# Clock_circuit.net
KiCad netlist of a schematic drawn in Altium Designer
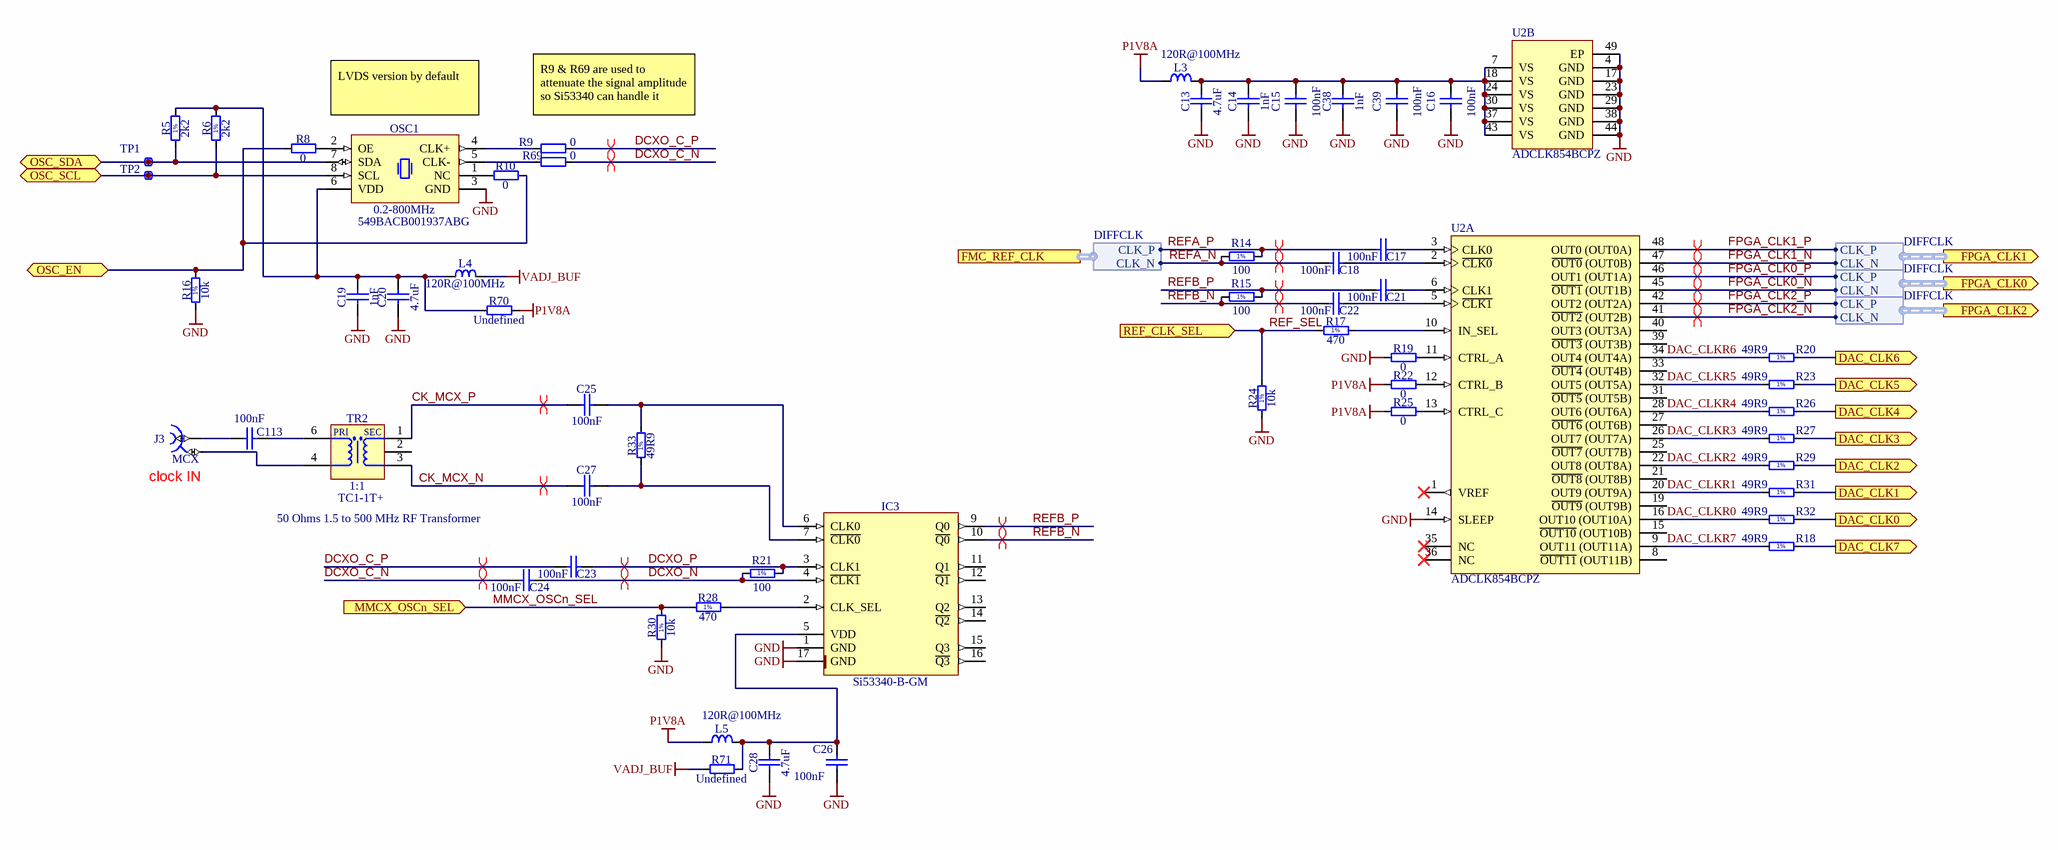
[diagram p0: Clock_circuit.SchDoc]

(export (version "E")
  (design (tool "Eeschema 10.0.6"))
  (components
    (comp (ref "C13")
      (value "4.7uF")
      (footprint "CAPC2012X135N")
      (description "Non-polarised capacitor")
      (fields
        (field (name "PART NUMBER") "CC0805_4.7UF_10V_10%_X5R")
        (field (name "VOLTAGE") "10V")
        (field (name "AUTHOR") "CERN DEM JLC")
      )
      (libsource (lib "Capacitors") (part "Capacitor - non polarized"))
    )
    (comp (ref "C14")
      (value "1nF")
      (footprint "CAPC1005X55N")
      (description "Non-polarised capacitor")
      (fields
        (field (name "PART NUMBER") "CC0402_1NF_50V_10%_X7R")
        (field (name "VOLTAGE") "50V")
        (field (name "AUTHOR") "CERN DEM JLC")
      )
      (libsource (lib "Capacitors") (part "Capacitor - non polarized"))
    )
    (comp (ref "C15")
      (value "100nF")
      (footprint "CAPC1005X55N")
      (description "Non-polarised capacitor")
      (fields
        (field (name "PART NUMBER") "CC0402_100NF_16V_10%_X5R")
        (field (name "VOLTAGE") "16V")
        (field (name "AUTHOR") "CERN DEM JLC")
      )
      (libsource (lib "Capacitors") (part "Capacitor - non polarized"))
    )
    (comp (ref "C16")
      (value "100nF")
      (footprint "CAPC1005X55N")
      (description "Non-polarised capacitor")
      (fields
        (field (name "PART NUMBER") "CC0402_100NF_16V_10%_X5R")
        (field (name "VOLTAGE") "16V")
        (field (name "AUTHOR") "CERN DEM JLC")
      )
      (libsource (lib "Capacitors") (part "Capacitor - non polarized"))
    )
    (comp (ref "C17")
      (value "100nF")
      (footprint "CAPC1005X55N")
      (description "Non-polarised capacitor")
      (fields
        (field (name "PART NUMBER") "CC0402_100NF_16V_10%_X5R")
        (field (name "VOLTAGE") "16V")
        (field (name "AUTHOR") "CERN DEM JLC")
      )
      (libsource (lib "Capacitors") (part "Capacitor - non polarized"))
    )
    (comp (ref "C18")
      (value "100nF")
      (footprint "CAPC1005X55N")
      (description "Non-polarised capacitor")
      (fields
        (field (name "PART NUMBER") "CC0402_100NF_16V_10%_X5R")
        (field (name "VOLTAGE") "16V")
        (field (name "AUTHOR") "CERN DEM JLC")
      )
      (libsource (lib "Capacitors") (part "Capacitor - non polarized"))
    )
    (comp (ref "C19")
      (value "1nF")
      (footprint "CAPC1005X55N")
      (description "Non-polarised capacitor")
      (fields
        (field (name "PART NUMBER") "CC0402_1NF_50V_10%_X7R")
        (field (name "VOLTAGE") "50V")
        (field (name "AUTHOR") "CERN DEM JLC")
      )
      (libsource (lib "Capacitors") (part "Capacitor - non polarized"))
    )
    (comp (ref "C20")
      (value "4.7uF")
      (footprint "CAPC2012X135N")
      (description "Non-polarised capacitor")
      (fields
        (field (name "PART NUMBER") "CC0805_4.7UF_10V_10%_X5R")
        (field (name "VOLTAGE") "10V")
        (field (name "AUTHOR") "CERN DEM JLC")
      )
      (libsource (lib "Capacitors") (part "Capacitor - non polarized"))
    )
    (comp (ref "C21")
      (value "100nF")
      (footprint "CAPC1005X55N")
      (description "Non-polarised capacitor")
      (fields
        (field (name "PART NUMBER") "CC0402_100NF_16V_10%_X5R")
        (field (name "VOLTAGE") "16V")
        (field (name "AUTHOR") "CERN DEM JLC")
      )
      (libsource (lib "Capacitors") (part "Capacitor - non polarized"))
    )
    (comp (ref "C22")
      (value "100nF")
      (footprint "CAPC1005X55N")
      (description "Non-polarised capacitor")
      (fields
        (field (name "PART NUMBER") "CC0402_100NF_16V_10%_X5R")
        (field (name "VOLTAGE") "16V")
        (field (name "AUTHOR") "CERN DEM JLC")
      )
      (libsource (lib "Capacitors") (part "Capacitor - non polarized"))
    )
    (comp (ref "C23")
      (value "100nF")
      (footprint "CAPC1005X55N")
      (description "Non-polarised capacitor")
      (fields
        (field (name "PART NUMBER") "CC0402_100NF_16V_10%_X5R")
        (field (name "VOLTAGE") "16V")
        (field (name "AUTHOR") "CERN DEM JLC")
      )
      (libsource (lib "Capacitors") (part "Capacitor - non polarized"))
    )
    (comp (ref "C24")
      (value "100nF")
      (footprint "CAPC1005X55N")
      (description "Non-polarised capacitor")
      (fields
        (field (name "PART NUMBER") "CC0402_100NF_16V_10%_X5R")
        (field (name "VOLTAGE") "16V")
        (field (name "AUTHOR") "CERN DEM JLC")
      )
      (libsource (lib "Capacitors") (part "Capacitor - non polarized"))
    )
    (comp (ref "C25")
      (value "100nF")
      (footprint "CAPC1005X55N")
      (description "Non-polarised capacitor")
      (fields
        (field (name "PART NUMBER") "CC0402_100NF_16V_10%_X5R")
        (field (name "VOLTAGE") "16V")
        (field (name "AUTHOR") "CERN DEM JLC")
      )
      (libsource (lib "Capacitors") (part "Capacitor - non polarized"))
    )
    (comp (ref "C26")
      (value "100nF")
      (footprint "CAPC1005X55N")
      (description "Non-polarised capacitor")
      (fields
        (field (name "PART NUMBER") "CC0402_100NF_16V_10%_X5R")
        (field (name "VOLTAGE") "16V")
        (field (name "AUTHOR") "CERN DEM JLC")
      )
      (libsource (lib "Capacitors") (part "Capacitor - non polarized"))
    )
    (comp (ref "C27")
      (value "100nF")
      (footprint "CAPC1005X55N")
      (description "Non-polarised capacitor")
      (fields
        (field (name "PART NUMBER") "CC0402_100NF_16V_10%_X5R")
        (field (name "VOLTAGE") "16V")
        (field (name "AUTHOR") "CERN DEM JLC")
      )
      (libsource (lib "Capacitors") (part "Capacitor - non polarized"))
    )
    (comp (ref "C28")
      (value "4.7uF")
      (footprint "CAPC2012X135N")
      (description "Non-polarised capacitor")
      (fields
        (field (name "PART NUMBER") "CC0805_4.7UF_10V_10%_X5R")
        (field (name "VOLTAGE") "10V")
        (field (name "AUTHOR") "CERN DEM JLC")
      )
      (libsource (lib "Capacitors") (part "Capacitor - non polarized"))
    )
    (comp (ref "C38")
      (value "1nF")
      (footprint "CAPC1005X55N")
      (description "Non-polarised capacitor")
      (fields
        (field (name "PART NUMBER") "CC0402_1NF_50V_10%_X7R")
        (field (name "VOLTAGE") "50V")
        (field (name "AUTHOR") "CERN DEM JLC")
      )
      (libsource (lib "Capacitors") (part "Capacitor - non polarized"))
    )
    (comp (ref "C39")
      (value "100nF")
      (footprint "CAPC1005X55N")
      (description "Non-polarised capacitor")
      (fields
        (field (name "PART NUMBER") "CC0402_100NF_16V_10%_X5R")
        (field (name "VOLTAGE") "16V")
        (field (name "AUTHOR") "CERN DEM JLC")
      )
      (libsource (lib "Capacitors") (part "Capacitor - non polarized"))
    )
    (comp (ref "C113")
      (value "100nF")
      (footprint "CAPC0603X33N")
      (description "Non-polarised capacitor")
      (fields
        (field (name "PART NUMBER") "CC0201_100NF_6.3V_10%_X5R")
        (field (name "VOLTAGE") "6.3V")
        (field (name "AUTHOR") "CERN DEM JLC")
      )
      (libsource (lib "Capacitors") (part "Capacitor - non polarized"))
    )
    (comp (ref "IC3")
      (value "Si53340-B-GM")
      (footprint "QFN50P300X300X90-17N-S175")
      (description "Low-Jitter LVDS Fanout Clock Buffers, 10-Output,  Any-Input, Any-Frequency up to 1250MHz")
      (fields (field (name "MANUFACTURER") "SILICON LABS") (field (name "AUTHOR") "CERN DEM MR"))
      (libsource (lib "ICs And Semiconductors") (part "Si53340"))
    )
    (comp (ref "J3")
      (value "MCX")
      (footprint "AMPHENOL_919-383J-51A")
      (fields
        (field (name "PART NUMBER") "AMPHENOL_919-383J-51A")
        (field (name "MANUFACTURER") "AMPHENOL")
        (field (name "MANUFACTURER PART NUMBER") "919-383J-51A")
        (field (name "AUTHOR") "CERN DEM BC")
      )
      (libsource (lib "Connectors") (part "Coax_1Female_1Shield"))
    )
    (comp (ref "L3")
      (value "120R@100MHz")
      (footprint "INDC1608X95N")
      (description "Inductor")
      (fields
        (field (name "PART NUMBER") "IND0603_MURATA_BLM18PG121SN1D")
        (field (name "POWER") "2A")
        (field (name "AUTHOR") "CERN DEM BC")
      )
      (libsource (lib "Inductors & Transformers") (part "Inductor"))
    )
    (comp (ref "L4")
      (value "120R@100MHz")
      (footprint "INDC1608X65N")
      (description "Inductor")
      (fields
        (field (name "PART NUMBER") "IND0603_MURATA_BLM18SG121TN1D")
        (field (name "POWER") "3A")
        (field (name "AUTHOR") "CERN DEM JLC")
      )
      (libsource (lib "Inductors & Transformers") (part "Inductor"))
    )
    (comp (ref "L5")
      (value "120R@100MHz")
      (footprint "INDC1608X95N")
      (description "Inductor")
      (fields
        (field (name "PART NUMBER") "IND0603_MURATA_BLM18PG121SN1D")
        (field (name "POWER") "2A")
        (field (name "AUTHOR") "CERN DEM BC")
      )
      (libsource (lib "Inductors & Transformers") (part "Inductor"))
    )
    (comp (ref "OSC1")
      (value "0.2-800MHz")
      (footprint "OSC_SILICON-LAB_SI549-A")
      (description "Ultra Low Jitter I2C Programmable Crystal Oscillator (XO), Si549 Series")
      (fields
        (field (name "PART NUMBER") "OSC_0.2-800MHZ_SILICON-LAB_549BACB001937ABG")
        (field (name "MANUFACTURER") "SILICON LABS")
        (field (name "MANUFACTURER PART NUMBER") "549BACB001937ABG")
        (field (name "AUTHOR") "CERN DEM JMW")
      )
      (libsource (lib "ICs And Semiconductors") (part "Oscillator SILICON-LAB_Si549-CD"))
    )
    (comp (ref "R5")
      (value "2k2")
      (footprint "RESC1005X40N")
      (description "Resistor - 1%")
      (fields
        (field (name "PART NUMBER") "R0402_2K2_1%_0.0625W_100PPM")
        (field (name "POWER") "0.0625W")
        (field (name "AUTHOR") "CERN DEM JLC")
      )
      (libsource (lib "Resistors") (part "Resistor - 1%"))
    )
    (comp (ref "R6")
      (value "2k2")
      (footprint "RESC1005X40N")
      (description "Resistor - 1%")
      (fields
        (field (name "PART NUMBER") "R0402_2K2_1%_0.0625W_100PPM")
        (field (name "POWER") "0.0625W")
        (field (name "AUTHOR") "CERN DEM JLC")
      )
      (libsource (lib "Resistors") (part "Resistor - 1%"))
    )
    (comp (ref "R8")
      (value "0")
      (footprint "RESC1005X40N")
      (description "Resistor")
      (fields
        (field (name "PART NUMBER") "R0402_0R_JUMPER")
        (field (name "MANUFACTURER") "GENERIC")
        (field (name "AUTHOR") "CERN DEM JLC")
      )
      (libsource (lib "Resistors") (part "Resistor"))
    )
    (comp (ref "R9")
      (value "0")
      (footprint "RESC1005X40N")
      (description "Resistor")
      (fields
        (field (name "PART NUMBER") "R0402_0R_JUMPER")
        (field (name "MANUFACTURER") "GENERIC")
        (field (name "AUTHOR") "CERN DEM JLC")
      )
      (libsource (lib "Resistors") (part "Resistor"))
    )
    (comp (ref "R10")
      (value "0")
      (footprint "RESC1005X40N")
      (description "Resistor")
      (fields
        (field (name "PART NUMBER") "R0402_0R_JUMPER")
        (field (name "MANUFACTURER") "GENERIC")
        (field (name "AUTHOR") "CERN DEM JLC")
      )
      (libsource (lib "Resistors") (part "Resistor"))
    )
    (comp (ref "R14")
      (value "100")
      (footprint "RESC0603X28N")
      (description "Resistor - 1%")
      (fields
        (field (name "PART NUMBER") "R0201_100R_1%_0.05W_200PPM")
        (field (name "POWER") "0.05W")
        (field (name "AUTHOR") "CERN DEM JLC")
      )
      (libsource (lib "Resistors") (part "Resistor - 1%"))
    )
    (comp (ref "R15")
      (value "100")
      (footprint "RESC0603X28N")
      (description "Resistor - 1%")
      (fields
        (field (name "PART NUMBER") "R0201_100R_1%_0.05W_200PPM")
        (field (name "POWER") "0.05W")
        (field (name "AUTHOR") "CERN DEM JLC")
      )
      (libsource (lib "Resistors") (part "Resistor - 1%"))
    )
    (comp (ref "R16")
      (value "10k")
      (footprint "RESC1005X40N")
      (description "Resistor - 1%")
      (fields
        (field (name "PART NUMBER") "R0402_10K_1%_0.0625W_100PPM")
        (field (name "POWER") "0.0625W")
        (field (name "AUTHOR") "CERN DEM JLC")
      )
      (libsource (lib "Resistors") (part "Resistor - 1%"))
    )
    (comp (ref "R17")
      (value "470")
      (footprint "RESC1005X40N")
      (description "Resistor - 1%")
      (fields
        (field (name "PART NUMBER") "R0402_470R_1%_0.0625W_100PPM")
        (field (name "POWER") "0.0625W")
        (field (name "AUTHOR") "CERN DEM JLC")
      )
      (libsource (lib "Resistors") (part "Resistor - 1%"))
    )
    (comp (ref "R18")
      (value "49R9")
      (footprint "RESC1005X40N")
      (description "Resistor - 1%")
      (fields
        (field (name "PART NUMBER") "R0402_49R9_1%_0.0625W_100PPM")
        (field (name "POWER") "0.0625W")
        (field (name "AUTHOR") "CERN DEM JLC")
      )
      (libsource (lib "Resistors") (part "Resistor - 1%"))
    )
    (comp (ref "R19")
      (value "0")
      (footprint "RESC1005X40N")
      (description "Resistor")
      (fields
        (field (name "PART NUMBER") "R0402_0R_JUMPER")
        (field (name "MANUFACTURER") "GENERIC")
        (field (name "AUTHOR") "CERN DEM JLC")
      )
      (libsource (lib "Resistors") (part "Resistor"))
    )
    (comp (ref "R20")
      (value "49R9")
      (footprint "RESC1005X40N")
      (description "Resistor - 1%")
      (fields
        (field (name "PART NUMBER") "R0402_49R9_1%_0.0625W_100PPM")
        (field (name "POWER") "0.0625W")
        (field (name "AUTHOR") "CERN DEM JLC")
      )
      (libsource (lib "Resistors") (part "Resistor - 1%"))
    )
    (comp (ref "R21")
      (value "100")
      (footprint "RESC0603X28N")
      (description "Resistor - 1%")
      (fields
        (field (name "PART NUMBER") "R0201_100R_1%_0.05W_200PPM")
        (field (name "POWER") "0.05W")
        (field (name "AUTHOR") "CERN DEM JLC")
      )
      (libsource (lib "Resistors") (part "Resistor - 1%"))
    )
    (comp (ref "R22")
      (value "0")
      (footprint "RESC1005X40N")
      (description "Resistor")
      (fields
        (field (name "PART NUMBER") "R0402_0R_JUMPER")
        (field (name "MANUFACTURER") "GENERIC")
        (field (name "AUTHOR") "CERN DEM JLC")
      )
      (libsource (lib "Resistors") (part "Resistor"))
    )
    (comp (ref "R23")
      (value "49R9")
      (footprint "RESC1005X40N")
      (description "Resistor - 1%")
      (fields
        (field (name "PART NUMBER") "R0402_49R9_1%_0.0625W_100PPM")
        (field (name "POWER") "0.0625W")
        (field (name "AUTHOR") "CERN DEM JLC")
      )
      (libsource (lib "Resistors") (part "Resistor - 1%"))
    )
    (comp (ref "R24")
      (value "10k")
      (footprint "RESC1005X40N")
      (description "Resistor - 1%")
      (fields
        (field (name "PART NUMBER") "R0402_10K_1%_0.0625W_100PPM")
        (field (name "POWER") "0.0625W")
        (field (name "AUTHOR") "CERN DEM JLC")
      )
      (libsource (lib "Resistors") (part "Resistor - 1%"))
    )
    (comp (ref "R25")
      (value "0")
      (footprint "RESC1005X40N")
      (description "Resistor")
      (fields
        (field (name "PART NUMBER") "R0402_0R_JUMPER")
        (field (name "MANUFACTURER") "GENERIC")
        (field (name "AUTHOR") "CERN DEM JLC")
      )
      (libsource (lib "Resistors") (part "Resistor"))
    )
    (comp (ref "R26")
      (value "49R9")
      (footprint "RESC1005X40N")
      (description "Resistor - 1%")
      (fields
        (field (name "PART NUMBER") "R0402_49R9_1%_0.0625W_100PPM")
        (field (name "POWER") "0.0625W")
        (field (name "AUTHOR") "CERN DEM JLC")
      )
      (libsource (lib "Resistors") (part "Resistor - 1%"))
    )
    (comp (ref "R27")
      (value "49R9")
      (footprint "RESC1005X40N")
      (description "Resistor - 1%")
      (fields
        (field (name "PART NUMBER") "R0402_49R9_1%_0.0625W_100PPM")
        (field (name "POWER") "0.0625W")
        (field (name "AUTHOR") "CERN DEM JLC")
      )
      (libsource (lib "Resistors") (part "Resistor - 1%"))
    )
    (comp (ref "R28")
      (value "470")
      (footprint "RESC1005X40N")
      (description "Resistor - 1%")
      (fields
        (field (name "PART NUMBER") "R0402_470R_1%_0.0625W_100PPM")
        (field (name "POWER") "0.0625W")
        (field (name "AUTHOR") "CERN DEM JLC")
      )
      (libsource (lib "Resistors") (part "Resistor - 1%"))
    )
    (comp (ref "R29")
      (value "49R9")
      (footprint "RESC1005X40N")
      (description "Resistor - 1%")
      (fields
        (field (name "PART NUMBER") "R0402_49R9_1%_0.0625W_100PPM")
        (field (name "POWER") "0.0625W")
        (field (name "AUTHOR") "CERN DEM JLC")
      )
      (libsource (lib "Resistors") (part "Resistor - 1%"))
    )
    (comp (ref "R30")
      (value "10k")
      (footprint "RESC1005X40N")
      (description "Resistor - 1%")
      (fields
        (field (name "PART NUMBER") "R0402_10K_1%_0.0625W_100PPM")
        (field (name "POWER") "0.0625W")
        (field (name "AUTHOR") "CERN DEM JLC")
      )
      (libsource (lib "Resistors") (part "Resistor - 1%"))
    )
    (comp (ref "R31")
      (value "49R9")
      (footprint "RESC1005X40N")
      (description "Resistor - 1%")
      (fields
        (field (name "PART NUMBER") "R0402_49R9_1%_0.0625W_100PPM")
        (field (name "POWER") "0.0625W")
        (field (name "AUTHOR") "CERN DEM JLC")
      )
      (libsource (lib "Resistors") (part "Resistor - 1%"))
    )
    (comp (ref "R32")
      (value "49R9")
      (footprint "RESC1005X40N")
      (description "Resistor - 1%")
      (fields
        (field (name "PART NUMBER") "R0402_49R9_1%_0.0625W_100PPM")
        (field (name "POWER") "0.0625W")
        (field (name "AUTHOR") "CERN DEM JLC")
      )
      (libsource (lib "Resistors") (part "Resistor - 1%"))
    )
    (comp (ref "R33")
      (value "49R9")
      (footprint "RESC1005X40N")
      (description "Resistor - 1%")
      (fields
        (field (name "PART NUMBER") "R0402_49R9_1%_0.0625W_100PPM")
        (field (name "POWER") "0.0625W")
        (field (name "AUTHOR") "CERN DEM JLC")
      )
      (libsource (lib "Resistors") (part "Resistor - 1%"))
    )
    (comp (ref "R69")
      (value "0")
      (footprint "RESC1005X40N")
      (description "Resistor")
      (fields
        (field (name "PART NUMBER") "R0402_0R_JUMPER")
        (field (name "MANUFACTURER") "GENERIC")
        (field (name "AUTHOR") "CERN DEM JLC")
      )
      (libsource (lib "Resistors") (part "Resistor"))
    )
    (comp (ref "R70")
      (value "Undefined")
      (footprint "RESC1608X55N")
      (description "Resistor")
      (fields (field (name "PART NUMBER") "R0603_NO-VALUE") (field (name "AUTHOR") "CERN DEM JLC"))
      (libsource (lib "Resistors") (part "Resistor"))
    )
    (comp (ref "R71")
      (value "Undefined")
      (footprint "RESC1608X55N")
      (description "Resistor")
      (fields (field (name "PART NUMBER") "R0603_NO-VALUE") (field (name "AUTHOR") "CERN DEM JLC"))
      (libsource (lib "Resistors") (part "Resistor"))
    )
    (comp (ref "TP1")
      (value "I2C SW SDA")
      (footprint "TPS127")
      (description "Test Point")
      (fields (field (name "PART NUMBER") "SMD_PAD_1.27X1.27MM") (field (name "AUTHOR") "CERN DEM JLC"))
      (libsource (lib "Eletro-mechanical") (part "Test Point"))
    )
    (comp (ref "TP2")
      (value "I2C SW SCL")
      (footprint "TPS127")
      (description "Test Point")
      (fields (field (name "PART NUMBER") "SMD_PAD_1.27X1.27MM") (field (name "AUTHOR") "CERN DEM JLC"))
      (libsource (lib "Eletro-mechanical") (part "Test Point"))
    )
    (comp (ref "TR2")
      (value "1:1")
      (footprint "XFMR_MINI-CIRCUITS_AT224-1")
      (description "50 Ohm  0.4 To 500MHz RF Transformers")
      (fields
        (field (name "PART NUMBER") "XFMR_MINI-CIRCUITS_TC1-1T+")
        (field (name "PART DESCRIPTION") "50 Ohms 1.5 to 500 MHz RF Transformer")
        (field (name "MANUFACTURER") "MINI-CIRCUITS")
        (field (name "MANUFACTURER PART NUMBER") "TC1-1T+")
        (field (name "AUTHOR") "CERN DEM JLC")
      )
      (libsource (lib "Inductors & Transformers") (part "XFMR_MINI-CIRCUITS_TC1-1+"))
    )
    (comp (ref "U2")
      (value "ADCLK854BCPZ")
      (footprint "ADI-CP-48-6_L")
      (fields (field (name "MANUFACTURER") "Analog Devices"))
      (libsource (lib "Altium Content Vault") (part "ADI-ADCLK854-CP-48-6"))
    )
  )
  (nets
    (net (code "3") (name "/CK_MCX_N") (class "Default")
      (node (ref "C27") (pin "1") (pinfunction "1_1") (pintype "passive"))
      (node (ref "TR2") (pin "3") (pinfunction "S_3") (pintype "passive"))
    )
    (net (code "4") (name "/CK_MCX_P") (class "Default")
      (node (ref "C25") (pin "1") (pinfunction "1_1") (pintype "passive"))
      (node (ref "TR2") (pin "1") (pinfunction "SDOT_1") (pintype "passive"))
    )
    (net (code "5") (name "/DAC_CLK0") (class "Default")
      (node (ref "R32") (pin "2") (pinfunction "2_2") (pintype "passive"))
    )
    (net (code "6") (name "/DAC_CLK1") (class "Default")
      (node (ref "R31") (pin "2") (pinfunction "2_2") (pintype "passive"))
    )
    (net (code "7") (name "/DAC_CLK2") (class "Default")
      (node (ref "R29") (pin "2") (pinfunction "2_2") (pintype "passive"))
    )
    (net (code "8") (name "/DAC_CLK3") (class "Default")
      (node (ref "R27") (pin "2") (pinfunction "2_2") (pintype "passive"))
    )
    (net (code "9") (name "/DAC_CLK4") (class "Default")
      (node (ref "R26") (pin "2") (pinfunction "2_2") (pintype "passive"))
    )
    (net (code "10") (name "/DAC_CLK5") (class "Default")
      (node (ref "R23") (pin "2") (pinfunction "2_2") (pintype "passive"))
    )
    (net (code "11") (name "/DAC_CLK6") (class "Default")
      (node (ref "R20") (pin "2") (pinfunction "2_2") (pintype "passive"))
    )
    (net (code "12") (name "/DAC_CLK7") (class "Default")
      (node (ref "R18") (pin "2") (pinfunction "2_2") (pintype "passive"))
    )
    (net (code "13") (name "/DAC_CLKR0") (class "Default")
      (node (ref "R32") (pin "1") (pinfunction "1_1") (pintype "passive"))
      (node (ref "U2") (pin "16") (pinfunction "OUT10_(OUT10A)_16") (pintype "tri_state"))
    )
    (net (code "14") (name "/DAC_CLKR1") (class "Default")
      (node (ref "R31") (pin "1") (pinfunction "1_1") (pintype "passive"))
      (node (ref "U2") (pin "20") (pinfunction "OUT9_(OUT9A)_20") (pintype "tri_state"))
    )
    (net (code "15") (name "/DAC_CLKR2") (class "Default")
      (node (ref "R29") (pin "1") (pinfunction "1_1") (pintype "passive"))
      (node (ref "U2") (pin "22") (pinfunction "OUT8_(OUT8A)_22") (pintype "tri_state"))
    )
    (net (code "16") (name "/DAC_CLKR3") (class "Default")
      (node (ref "R27") (pin "1") (pinfunction "1_1") (pintype "passive"))
      (node (ref "U2") (pin "26") (pinfunction "OUT7_(OUT7A)_26") (pintype "tri_state"))
    )
    (net (code "17") (name "/DAC_CLKR4") (class "Default")
      (node (ref "R26") (pin "1") (pinfunction "1_1") (pintype "passive"))
      (node (ref "U2") (pin "28") (pinfunction "OUT6_(OUT6A)_28") (pintype "tri_state"))
    )
    (net (code "18") (name "/DAC_CLKR5") (class "Default")
      (node (ref "R23") (pin "1") (pinfunction "1_1") (pintype "passive"))
      (node (ref "U2") (pin "32") (pinfunction "OUT5_(OUT5A)_32") (pintype "tri_state"))
    )
    (net (code "19") (name "/DAC_CLKR6") (class "Default")
      (node (ref "R20") (pin "1") (pinfunction "1_1") (pintype "passive"))
      (node (ref "U2") (pin "34") (pinfunction "OUT4_(OUT4A)_34") (pintype "tri_state"))
    )
    (net (code "20") (name "/DAC_CLKR7") (class "Default")
      (node (ref "R18") (pin "1") (pinfunction "1_1") (pintype "passive"))
      (node (ref "U2") (pin "9") (pinfunction "OUT11_(OUT11A)_9") (pintype "tri_state"))
    )
    (net (code "21") (name "/DCXO_C_N") (class "Default")
      (node (ref "C24") (pin "1") (pinfunction "1_1") (pintype "passive"))
      (node (ref "R69") (pin "2") (pinfunction "2_2") (pintype "passive"))
    )
    (net (code "22") (name "/DCXO_C_P") (class "Default")
      (node (ref "C23") (pin "1") (pinfunction "1_1") (pintype "passive"))
      (node (ref "R9") (pin "2") (pinfunction "2_2") (pintype "passive"))
    )
    (net (code "23") (name "/DCXO_N") (class "Default")
      (node (ref "C24") (pin "2") (pinfunction "2_2") (pintype "passive"))
      (node (ref "IC3") (pin "4") (pinfunction "~{CLK1}_4") (pintype "input"))
      (node (ref "R21") (pin "1") (pinfunction "1_1") (pintype "passive"))
    )
    (net (code "24") (name "/DCXO_P") (class "Default")
      (node (ref "C23") (pin "2") (pinfunction "2_2") (pintype "passive"))
      (node (ref "IC3") (pin "3") (pinfunction "CLK1_3") (pintype "input"))
      (node (ref "R21") (pin "2") (pinfunction "2_2") (pintype "passive"))
    )
    (net (code "25") (name "/FPGA_CLK0_N") (class "Default")
      (node (ref "U2") (pin "45") (pinfunction "~{OUT1}_(OUT1B)_45") (pintype "tri_state"))
    )
    (net (code "26") (name "/FPGA_CLK0_P") (class "Default")
      (node (ref "U2") (pin "46") (pinfunction "OUT1_(OUT1A)_46") (pintype "tri_state"))
    )
    (net (code "27") (name "/FPGA_CLK1_N") (class "Default")
      (node (ref "U2") (pin "47") (pinfunction "~{OUT0}_(OUT0B)_47") (pintype "tri_state"))
    )
    (net (code "28") (name "/FPGA_CLK1_P") (class "Default")
      (node (ref "U2") (pin "48") (pinfunction "OUT0_(OUT0A)_48") (pintype "tri_state"))
    )
    (net (code "30") (name "/FPGA_CLK2_N") (class "Default")
      (node (ref "U2") (pin "41") (pinfunction "~{OUT2}_(OUT2B)_41") (pintype "tri_state"))
    )
    (net (code "31") (name "/FPGA_CLK2_P") (class "Default")
      (node (ref "U2") (pin "42") (pinfunction "OUT2_(OUT2A)_42") (pintype "tri_state"))
    )
    (net (code "32") (name "/MMCX_OSCn_SEL") (class "Default")
      (node (ref "R28") (pin "1") (pinfunction "1_1") (pintype "passive"))
      (node (ref "R30") (pin "2") (pinfunction "2_2") (pintype "passive"))
    )
    (net (code "33") (name "/OSC_EN") (class "Default")
      (node (ref "R10") (pin "2") (pinfunction "2_2") (pintype "passive"))
      (node (ref "R16") (pin "2") (pinfunction "2_2") (pintype "passive"))
      (node (ref "R8") (pin "1") (pinfunction "1_1") (pintype "passive"))
    )
    (net (code "34") (name "/OSC_SCL") (class "Default")
      (node (ref "OSC1") (pin "8") (pinfunction "SCL_8") (pintype "input"))
      (node (ref "R6") (pin "1") (pinfunction "1_1") (pintype "passive"))
      (node (ref "TP2") (pin "1") (pinfunction "1_1") (pintype "bidirectional"))
    )
    (net (code "35") (name "/OSC_SDA") (class "Default")
      (node (ref "OSC1") (pin "7") (pinfunction "SDA_7") (pintype "bidirectional"))
      (node (ref "R5") (pin "1") (pinfunction "1_1") (pintype "passive"))
      (node (ref "TP1") (pin "1") (pinfunction "1_1") (pintype "bidirectional"))
    )
    (net (code "36") (name "/REFA_N") (class "Default")
      (node (ref "C18") (pin "1") (pinfunction "1_1") (pintype "passive"))
      (node (ref "R14") (pin "1") (pinfunction "1_1") (pintype "passive"))
    )
    (net (code "37") (name "/REFA_P") (class "Default")
      (node (ref "C17") (pin "1") (pinfunction "1_1") (pintype "passive"))
      (node (ref "R14") (pin "2") (pinfunction "2_2") (pintype "passive"))
    )
    (net (code "38") (name "/REFB_N") (class "Default")
      (node (ref "C22") (pin "1") (pinfunction "1_1") (pintype "passive"))
      (node (ref "IC3") (pin "10") (pinfunction "~{Q0}_10") (pintype "output"))
      (node (ref "R15") (pin "1") (pinfunction "1_1") (pintype "passive"))
    )
    (net (code "39") (name "/REFB_P") (class "Default")
      (node (ref "C21") (pin "1") (pinfunction "1_1") (pintype "passive"))
      (node (ref "IC3") (pin "9") (pinfunction "Q0_9") (pintype "output"))
      (node (ref "R15") (pin "2") (pinfunction "2_2") (pintype "passive"))
    )
    (net (code "40") (name "/REF_SEL") (class "Default")
      (node (ref "R17") (pin "1") (pinfunction "1_1") (pintype "passive"))
      (node (ref "R24") (pin "2") (pinfunction "2_2") (pintype "passive"))
    )
    (net (code "42") (name "GND") (class "Default")
      (node (ref "C13") (pin "1") (pinfunction "1_1") (pintype "passive"))
      (node (ref "C14") (pin "1") (pinfunction "1_1") (pintype "passive"))
      (node (ref "C15") (pin "1") (pinfunction "1_1") (pintype "passive"))
      (node (ref "C16") (pin "1") (pinfunction "1_1") (pintype "passive"))
      (node (ref "C19") (pin "1") (pinfunction "1_1") (pintype "passive"))
      (node (ref "C20") (pin "1") (pinfunction "1_1") (pintype "passive"))
      (node (ref "C26") (pin "1") (pinfunction "1_1") (pintype "passive"))
      (node (ref "C28") (pin "1") (pinfunction "1_1") (pintype "passive"))
      (node (ref "C38") (pin "1") (pinfunction "1_1") (pintype "passive"))
      (node (ref "C39") (pin "1") (pinfunction "1_1") (pintype "passive"))
      (node (ref "IC3") (pin "1") (pinfunction "GND_1") (pintype "power_in"))
      (node (ref "IC3") (pin "17") (pinfunction "GND_17") (pintype "power_in"))
      (node (ref "OSC1") (pin "3") (pinfunction "GND_3") (pintype "power_in"))
      (node (ref "R16") (pin "1") (pinfunction "1_1") (pintype "passive"))
      (node (ref "R19") (pin "1") (pinfunction "1_1") (pintype "passive"))
      (node (ref "R24") (pin "1") (pinfunction "1_1") (pintype "passive"))
      (node (ref "R30") (pin "1") (pinfunction "1_1") (pintype "passive"))
      (node (ref "U2") (pin "14") (pinfunction "SLEEP_14") (pintype "input"))
      (node (ref "U2") (pin "17") (pinfunction "GND_17") (pintype "power_in"))
      (node (ref "U2") (pin "23") (pinfunction "GND_23") (pintype "power_in"))
      (node (ref "U2") (pin "29") (pinfunction "GND_29") (pintype "power_in"))
      (node (ref "U2") (pin "38") (pinfunction "GND_38") (pintype "power_in"))
      (node (ref "U2") (pin "4") (pinfunction "GND_4") (pintype "power_in"))
      (node (ref "U2") (pin "44") (pinfunction "GND_44") (pintype "power_in"))
      (node (ref "U2") (pin "49") (pinfunction "EP_49") (pintype "power_in"))
    )
    (net (code "43") (name "Net-(C13-Pad2)") (class "Default")
      (node (ref "C13") (pin "2") (pinfunction "2_2") (pintype "passive"))
      (node (ref "C14") (pin "2") (pinfunction "2_2") (pintype "passive"))
      (node (ref "C15") (pin "2") (pinfunction "2_2") (pintype "passive"))
      (node (ref "C16") (pin "2") (pinfunction "2_2") (pintype "passive"))
      (node (ref "C38") (pin "2") (pinfunction "2_2") (pintype "passive"))
      (node (ref "C39") (pin "2") (pinfunction "2_2") (pintype "passive"))
      (node (ref "L3") (pin "1") (pinfunction "1_1") (pintype "passive"))
      (node (ref "U2") (pin "18") (pinfunction "VS_18") (pintype "power_in"))
      (node (ref "U2") (pin "24") (pinfunction "VS_24") (pintype "power_in"))
      (node (ref "U2") (pin "30") (pinfunction "VS_30") (pintype "power_in"))
      (node (ref "U2") (pin "37") (pinfunction "VS_37") (pintype "power_in"))
      (node (ref "U2") (pin "43") (pinfunction "VS_43") (pintype "power_in"))
      (node (ref "U2") (pin "7") (pinfunction "VS_7") (pintype "power_in"))
    )
    (net (code "44") (name "Net-(C113-Pad2)") (class "Default")
      (node (ref "C113") (pin "2") (pinfunction "2_2") (pintype "passive"))
      (node (ref "J3") (pin "1") (pinfunction "1_1") (pintype "bidirectional"))
    )
    (net (code "45") (name "Net-(IC3-CLK0)") (class "Default")
      (node (ref "C25") (pin "2") (pinfunction "2_2") (pintype "passive"))
      (node (ref "IC3") (pin "6") (pinfunction "CLK0_6") (pintype "input"))
      (node (ref "R33") (pin "2") (pinfunction "2_2") (pintype "passive"))
    )
    (net (code "46") (name "Net-(IC3-CLK_SEL)") (class "Default")
      (node (ref "IC3") (pin "2") (pinfunction "CLK_SEL_2") (pintype "input"))
      (node (ref "R28") (pin "2") (pinfunction "2_2") (pintype "passive"))
    )
    (net (code "47") (name "Net-(IC3-VDD)") (class "Default")
      (node (ref "C26") (pin "2") (pinfunction "2_2") (pintype "passive"))
      (node (ref "C28") (pin "2") (pinfunction "2_2") (pintype "passive"))
      (node (ref "IC3") (pin "5") (pinfunction "VDD_5") (pintype "power_in"))
      (node (ref "L5") (pin "1") (pinfunction "1_1") (pintype "passive"))
      (node (ref "R71") (pin "2") (pinfunction "2_2") (pintype "passive"))
    )
    (net (code "48") (name "Net-(IC3-~{CLK0})") (class "Default")
      (node (ref "C27") (pin "2") (pinfunction "2_2") (pintype "passive"))
      (node (ref "IC3") (pin "7") (pinfunction "~{CLK0}_7") (pintype "input"))
      (node (ref "R33") (pin "1") (pinfunction "1_1") (pintype "passive"))
    )
    (net (code "49") (name "Net-(OSC1-CLK+)") (class "Default")
      (node (ref "OSC1") (pin "4") (pinfunction "CLK+_4") (pintype "output"))
      (node (ref "R9") (pin "1") (pinfunction "1_1") (pintype "passive"))
    )
    (net (code "50") (name "Net-(OSC1-CLK-)") (class "Default")
      (node (ref "OSC1") (pin "5") (pinfunction "CLK-_5") (pintype "output"))
      (node (ref "R69") (pin "1") (pinfunction "1_1") (pintype "passive"))
    )
    (net (code "51") (name "Net-(OSC1-NC)") (class "Default")
      (node (ref "OSC1") (pin "1") (pinfunction "NC_1") (pintype "passive"))
      (node (ref "R10") (pin "1") (pinfunction "1_1") (pintype "passive"))
    )
    (net (code "52") (name "Net-(OSC1-OE)") (class "Default")
      (node (ref "OSC1") (pin "2") (pinfunction "OE_2") (pintype "input"))
      (node (ref "R8") (pin "2") (pinfunction "2_2") (pintype "passive"))
    )
    (net (code "53") (name "Net-(OSC1-VDD)") (class "Default")
      (node (ref "C19") (pin "2") (pinfunction "2_2") (pintype "passive"))
      (node (ref "C20") (pin "2") (pinfunction "2_2") (pintype "passive"))
      (node (ref "L4") (pin "2") (pinfunction "2_2") (pintype "passive"))
      (node (ref "OSC1") (pin "6") (pinfunction "VDD_6") (pintype "power_in"))
      (node (ref "R5") (pin "2") (pinfunction "2_2") (pintype "passive"))
      (node (ref "R6") (pin "2") (pinfunction "2_2") (pintype "passive"))
      (node (ref "R70") (pin "1") (pinfunction "1_1") (pintype "passive"))
    )
    (net (code "54") (name "Net-(TR2-P)") (class "Default")
      (node (ref "J3") (pin "2") (pinfunction "2_2") (pintype "bidirectional"))
      (node (ref "TR2") (pin "4") (pinfunction "P_4") (pintype "passive"))
    )
    (net (code "55") (name "Net-(TR2-PDOT)") (class "Default")
      (node (ref "C113") (pin "1") (pinfunction "1_1") (pintype "passive"))
      (node (ref "TR2") (pin "6") (pinfunction "PDOT_6") (pintype "passive"))
    )
    (net (code "56") (name "Net-(U2A-CLK0)") (class "Default")
      (node (ref "C17") (pin "2") (pinfunction "2_2") (pintype "passive"))
      (node (ref "U2") (pin "3") (pinfunction "CLK0_3") (pintype "input"))
    )
    (net (code "57") (name "Net-(U2A-CLK1)") (class "Default")
      (node (ref "C21") (pin "2") (pinfunction "2_2") (pintype "passive"))
      (node (ref "U2") (pin "6") (pinfunction "CLK1_6") (pintype "input"))
    )
    (net (code "58") (name "Net-(U2A-CTRL_A)") (class "Default")
      (node (ref "R19") (pin "2") (pinfunction "2_2") (pintype "passive"))
      (node (ref "U2") (pin "11") (pinfunction "CTRL_A_11") (pintype "input"))
    )
    (net (code "59") (name "Net-(U2A-CTRL_B)") (class "Default")
      (node (ref "R22") (pin "2") (pinfunction "2_2") (pintype "passive"))
      (node (ref "U2") (pin "12") (pinfunction "CTRL_B_12") (pintype "input"))
    )
    (net (code "60") (name "Net-(U2A-CTRL_C)") (class "Default")
      (node (ref "R25") (pin "2") (pinfunction "2_2") (pintype "passive"))
      (node (ref "U2") (pin "13") (pinfunction "CTRL_C_13") (pintype "input"))
    )
    (net (code "61") (name "Net-(U2A-IN_SEL)") (class "Default")
      (node (ref "R17") (pin "2") (pinfunction "2_2") (pintype "passive"))
      (node (ref "U2") (pin "10") (pinfunction "IN_SEL_10") (pintype "input"))
    )
    (net (code "62") (name "Net-(U2A-~{CLK0})") (class "Default")
      (node (ref "C18") (pin "2") (pinfunction "2_2") (pintype "passive"))
      (node (ref "U2") (pin "2") (pinfunction "~{CLK0}_2") (pintype "input"))
    )
    (net (code "63") (name "Net-(U2A-~{CLK1})") (class "Default")
      (node (ref "C22") (pin "2") (pinfunction "2_2") (pintype "passive"))
      (node (ref "U2") (pin "5") (pinfunction "~{CLK1}_5") (pintype "input"))
    )
    (net (code "64") (name "P1V8A") (class "Default")
      (node (ref "L3") (pin "2") (pinfunction "2_2") (pintype "passive"))
      (node (ref "L5") (pin "2") (pinfunction "2_2") (pintype "passive"))
      (node (ref "R22") (pin "1") (pinfunction "1_1") (pintype "passive"))
      (node (ref "R25") (pin "1") (pinfunction "1_1") (pintype "passive"))
      (node (ref "R70") (pin "2") (pinfunction "2_2") (pintype "passive"))
    )
    (net (code "65") (name "VADJ_BUF") (class "Default")
      (node (ref "L4") (pin "1") (pinfunction "1_1") (pintype "passive"))
      (node (ref "R71") (pin "1") (pinfunction "1_1") (pintype "passive"))
    )
    (net (code "66") (name "unconnected-(IC3-Q1-Pad11)") (class "Default")
      (node (ref "IC3") (pin "11") (pinfunction "Q1_11") (pintype "output"))
    )
    (net (code "67") (name "unconnected-(IC3-Q2-Pad13)") (class "Default")
      (node (ref "IC3") (pin "13") (pinfunction "Q2_13") (pintype "output"))
    )
    (net (code "68") (name "unconnected-(IC3-Q3-Pad15)") (class "Default")
      (node (ref "IC3") (pin "15") (pinfunction "Q3_15") (pintype "output"))
    )
    (net (code "69") (name "unconnected-(IC3-~{Q1}-Pad12)") (class "Default")
      (node (ref "IC3") (pin "12") (pinfunction "~{Q1}_12") (pintype "output"))
    )
    (net (code "70") (name "unconnected-(IC3-~{Q2}-Pad14)") (class "Default")
      (node (ref "IC3") (pin "14") (pinfunction "~{Q2}_14") (pintype "output"))
    )
    (net (code "71") (name "unconnected-(IC3-~{Q3}-Pad16)") (class "Default")
      (node (ref "IC3") (pin "16") (pinfunction "~{Q3}_16") (pintype "output"))
    )
    (net (code "72") (name "unconnected-(TR2-NU-Pad2)") (class "Default")
      (node (ref "TR2") (pin "2") (pinfunction "NU_2") (pintype "passive"))
    )
    (net (code "73") (name "unconnected-(U2A-NC-Pad35)") (class "Default")
      (node (ref "U2") (pin "35") (pinfunction "NC_35") (pintype "passive+no_connect"))
    )
    (net (code "74") (name "unconnected-(U2A-NC-Pad36)") (class "Default")
      (node (ref "U2") (pin "36") (pinfunction "NC_36") (pintype "passive+no_connect"))
    )
    (net (code "75") (name "unconnected-(U2A-OUT3_(OUT3A)-Pad40)") (class "Default")
      (node (ref "U2") (pin "40") (pinfunction "OUT3_(OUT3A)_40") (pintype "tri_state"))
    )
    (net (code "76") (name "unconnected-(U2A-VREF-Pad1)") (class "Default")
      (node (ref "U2") (pin "1") (pinfunction "VREF_1") (pintype "output+no_connect"))
    )
    (net (code "77") (name "unconnected-(U2A-~{OUT3}_(OUT3B)-Pad39)") (class "Default")
      (node (ref "U2") (pin "39") (pinfunction "~{OUT3}_(OUT3B)_39") (pintype "tri_state"))
    )
    (net (code "78") (name "unconnected-(U2A-~{OUT4}_(OUT4B)-Pad33)") (class "Default")
      (node (ref "U2") (pin "33") (pinfunction "~{OUT4}_(OUT4B)_33") (pintype "tri_state"))
    )
    (net (code "79") (name "unconnected-(U2A-~{OUT5}_(OUT5B)-Pad31)") (class "Default")
      (node (ref "U2") (pin "31") (pinfunction "~{OUT5}_(OUT5B)_31") (pintype "tri_state"))
    )
    (net (code "80") (name "unconnected-(U2A-~{OUT6}_(OUT6B)-Pad27)") (class "Default")
      (node (ref "U2") (pin "27") (pinfunction "~{OUT6}_(OUT6B)_27") (pintype "tri_state"))
    )
    (net (code "81") (name "unconnected-(U2A-~{OUT7}_(OUT7B)-Pad25)") (class "Default")
      (node (ref "U2") (pin "25") (pinfunction "~{OUT7}_(OUT7B)_25") (pintype "tri_state"))
    )
    (net (code "82") (name "unconnected-(U2A-~{OUT8}_(OUT8B)-Pad21)") (class "Default")
      (node (ref "U2") (pin "21") (pinfunction "~{OUT8}_(OUT8B)_21") (pintype "tri_state"))
    )
    (net (code "83") (name "unconnected-(U2A-~{OUT9}_(OUT9B)-Pad19)") (class "Default")
      (node (ref "U2") (pin "19") (pinfunction "~{OUT9}_(OUT9B)_19") (pintype "tri_state"))
    )
    (net (code "84") (name "unconnected-(U2A-~{OUT10}_(OUT10B)-Pad15)") (class "Default")
      (node (ref "U2") (pin "15") (pinfunction "~{OUT10}_(OUT10B)_15") (pintype "tri_state"))
    )
    (net (code "85") (name "unconnected-(U2A-~{OUT11}_(OUT11B)-Pad8)") (class "Default")
      (node (ref "U2") (pin "8") (pinfunction "~{OUT11}_(OUT11B)_8") (pintype "tri_state"))
    )
  )
)
